# SCH_DC_Speed_controller_PWM_avarage_volt.net
KiCad netlist of a schematic drawn in EasyEDA
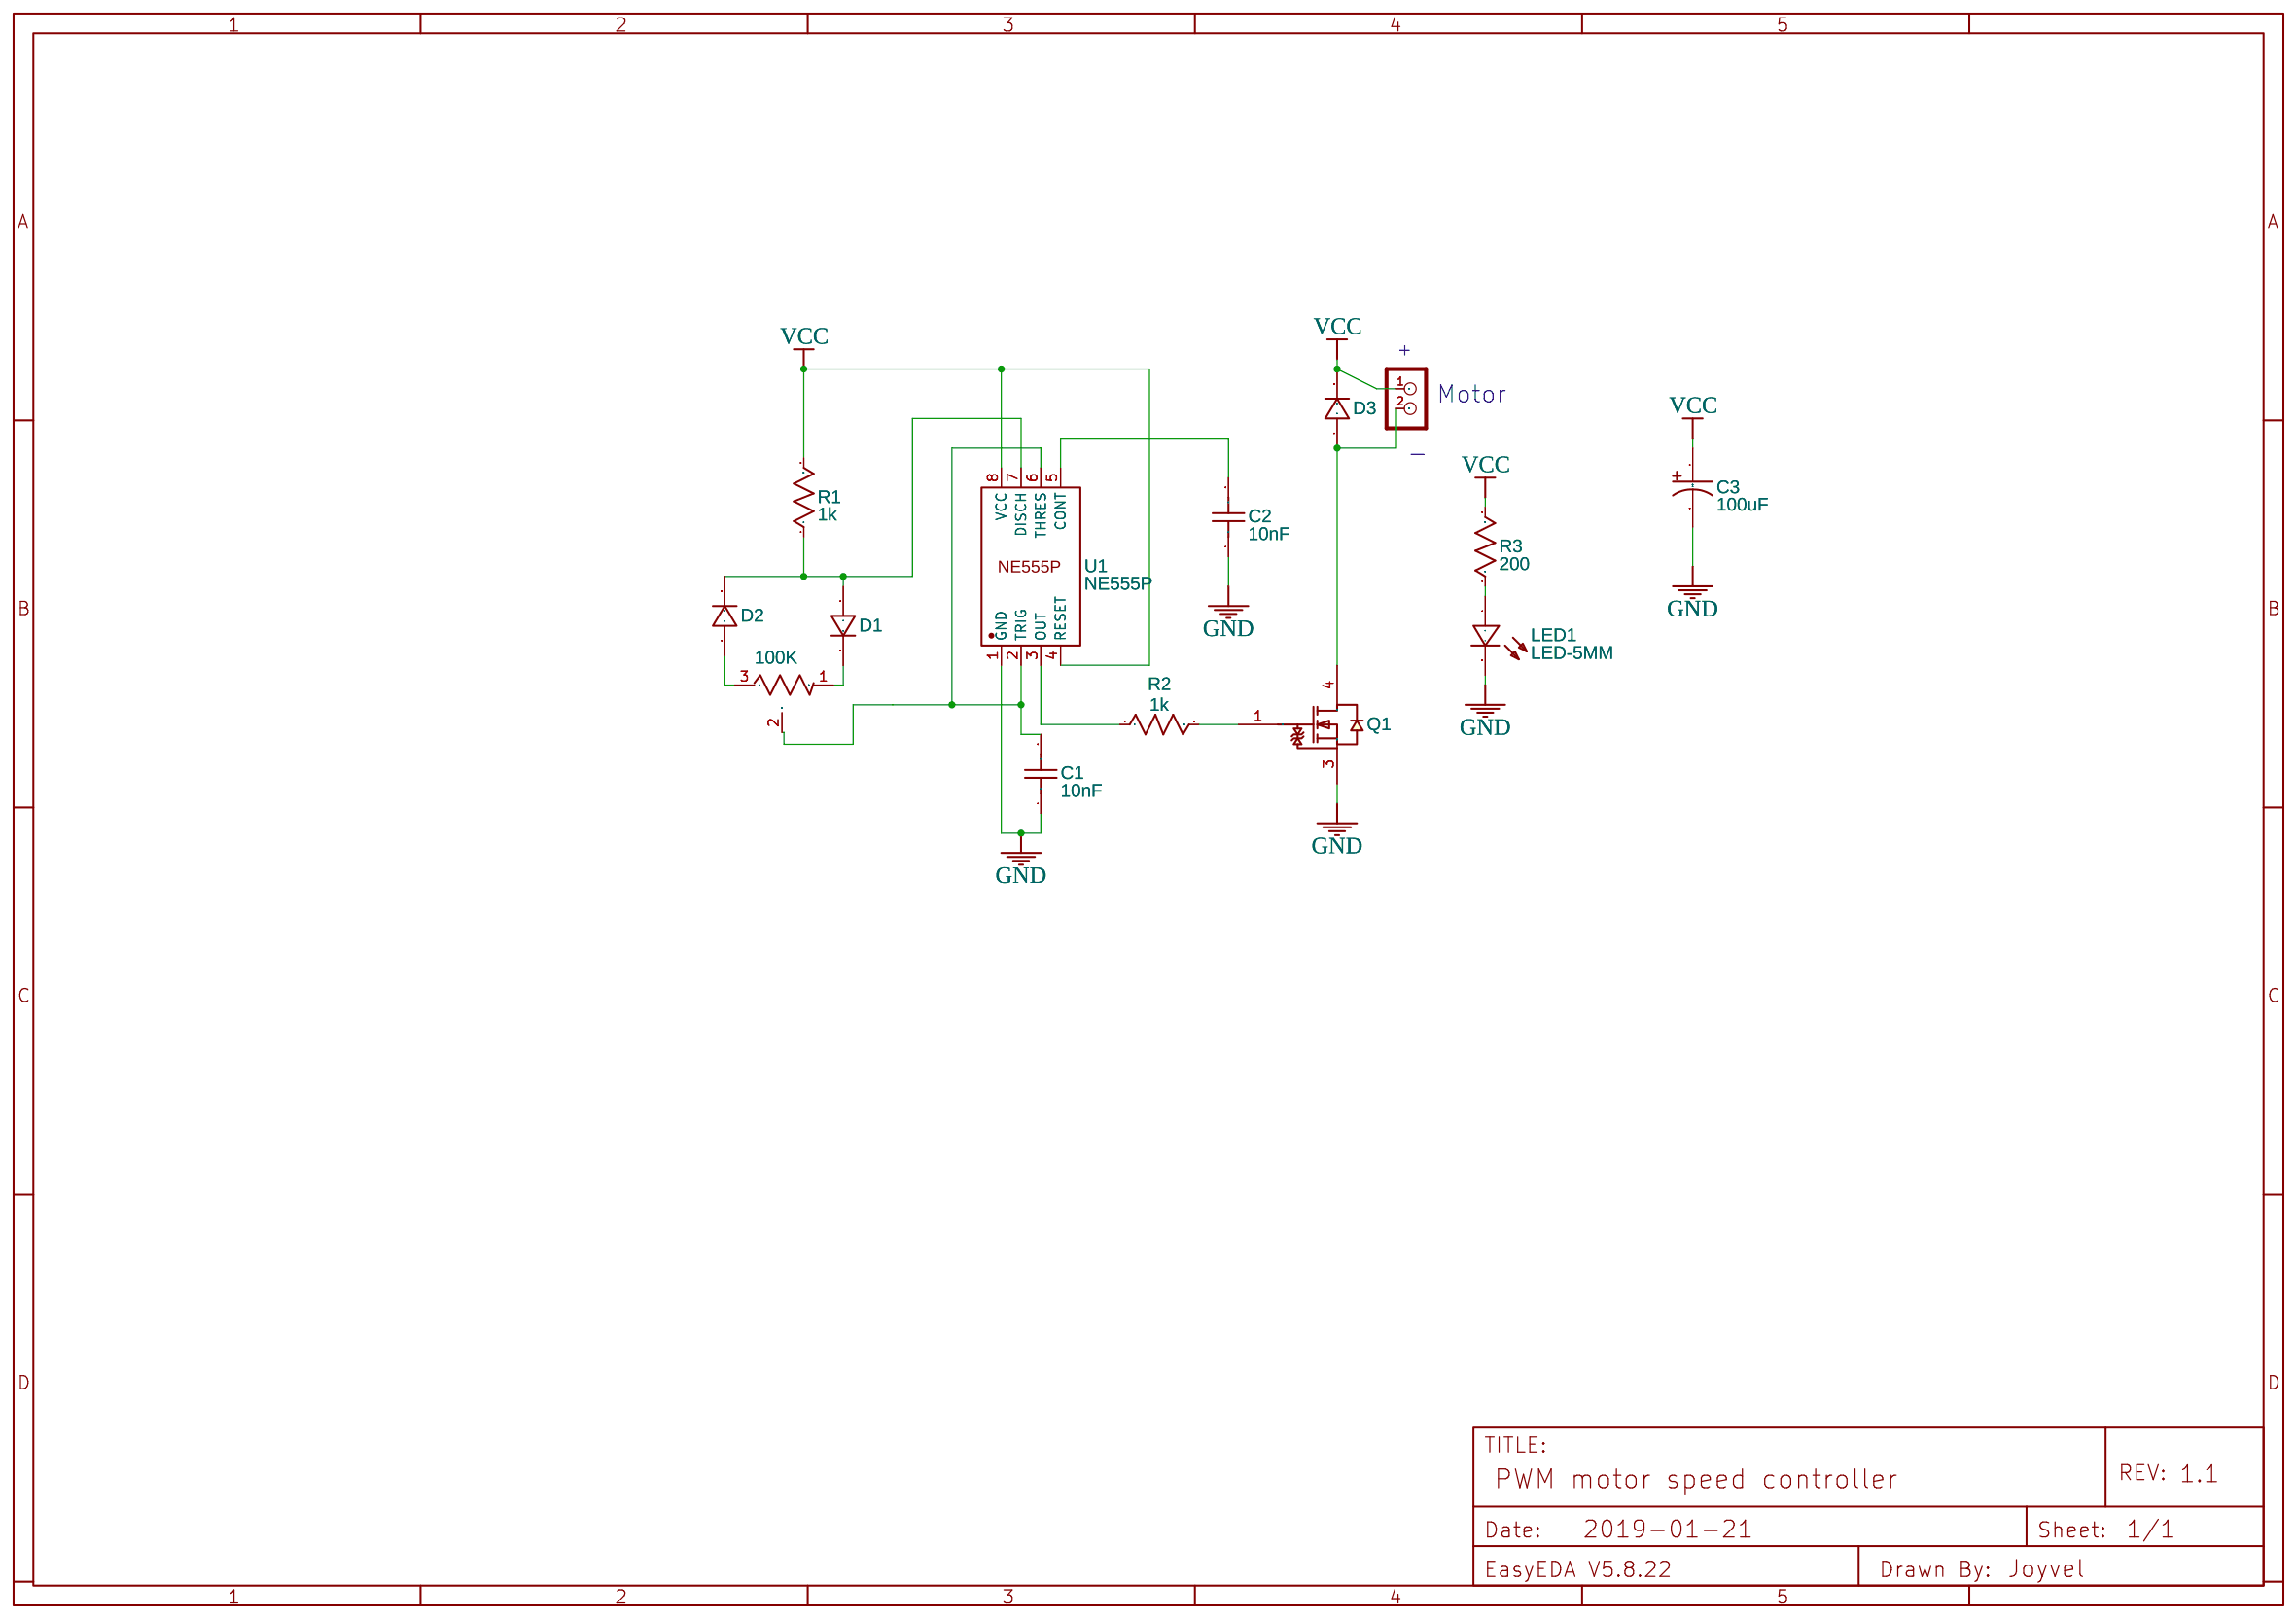
[diagram p0: schematic sheet]

(export (version "E")
  (design (tool "Eeschema 10.0.6"))
  (components
    (comp (ref "100K")
      (value "100K")
      (fields (field (name "Manufacturer Part") "?"))
      (libsource (lib "") (part "Unknown_405_340"))
    )
    (comp (ref "C1")
      (value "10nF")
      (fields (field (name "Manufacturer Part") "?"))
      (libsource (lib "") (part "Cap_RAD-0.1_US"))
    )
    (comp (ref "C2")
      (value "10nF")
      (fields (field (name "Manufacturer Part") "?"))
      (libsource (lib "") (part "Cap_RAD-0.1_US"))
    )
    (comp (ref "C3")
      (value "100uF")
      (fields (field (name "Manufacturer Part") "?"))
      (libsource (lib "") (part "Cap_Electrolytic(TH)_D3.0XF1.5_US"))
    )
    (comp (ref "D1")
      (value "1N4448")
      (fields (field (name "Manufacturer") "SEMTECH"))
      (libsource (lib "") (part "Unknown_420_310"))
    )
    (comp (ref "D2")
      (value "1N4448")
      (fields (field (name "Manufacturer") "SEMTECH"))
      (libsource (lib "") (part "Unknown_360_305"))
    )
    (comp (ref "D3")
      (value "0")
      (fields (field (name "Manufacturer Part") "1N4448") (field (name "Manufacturer") "SEMTECH"))
      (libsource (lib "") (part "Unknown_670_200"))
    )
    (comp (ref "J1")
      (value "CON_TERMINAL_BLOCK_02")
      (fields (field (name "Manufacturer Part") "?"))
      (libsource (lib "") (part "Unknown_705_195"))
    )
    (comp (ref "LED1")
      (value "LED-5MM")
      (fields (field (name "Manufacturer Part") "5AR2ST10") (field (name "Manufacturer") "EVERLIGHT"))
      (libsource (lib "") (part "Unknown_750_315"))
    )
    (comp (ref "Q1")
      (value "2SK4065-DL-1E")
      (fields (field (name "Manufacturer Part") "?"))
      (libsource (lib "") (part "Unknown_650_360"))
    )
    (comp (ref "R1")
      (value "1k")
      (fields (field (name "Manufacturer Part") "?"))
      (libsource (lib "") (part "Res_AXIAL-0.3(1/8W)_US"))
    )
    (comp (ref "R2")
      (value "1k")
      (fields (field (name "Manufacturer Part") "?"))
      (libsource (lib "") (part "Res_AXIAL-0.3(1/8W)_US_1"))
    )
    (comp (ref "R3")
      (value "200")
      (fields (field (name "Manufacturer Part") "?"))
      (libsource (lib "") (part "Res_AXIAL-0.3(1/8W)_US"))
    )
    (comp (ref "U1")
      (value "NE555P")
      (fields (field (name "Manufacturer") "TI"))
      (libsource (lib "") (part "Unknown_515_280"))
    )
  )
  (nets
    (net (code "1") (name "GND") (class "Default")
      (node (ref "C1") (pin "1") (pinfunction "1_1") (pintype "unspecified"))
      (node (ref "C2") (pin "1") (pinfunction "1_1") (pintype "unspecified"))
      (node (ref "C3") (pin "2") (pinfunction "2_2") (pintype "unspecified"))
      (node (ref "LED1") (pin "2") (pinfunction "-_2") (pintype "unspecified"))
      (node (ref "Q1") (pin "3") (pinfunction "S_3") (pintype "unspecified"))
      (node (ref "U1") (pin "1") (pinfunction "GND_1") (pintype "unspecified"))
    )
    (net (code "2") (name "Net-(D1-A)") (class "Default")
      (node (ref "D1") (pin "1") (pinfunction "A_1") (pintype "unspecified"))
      (node (ref "D2") (pin "2") (pinfunction "K_2") (pintype "unspecified"))
      (node (ref "R1") (pin "1") (pinfunction "1_1") (pintype "unspecified"))
      (node (ref "U1") (pin "7") (pinfunction "DISCH_7") (pintype "unspecified"))
    )
    (net (code "3") (name "Net-(D1-K)") (class "Default")
      (node (ref "100K") (pin "1") (pinfunction "1_1") (pintype "unspecified"))
      (node (ref "D1") (pin "2") (pinfunction "K_2") (pintype "unspecified"))
    )
    (net (code "4") (name "Net-(D2-A)") (class "Default")
      (node (ref "100K") (pin "3") (pinfunction "3_3") (pintype "unspecified"))
      (node (ref "D2") (pin "1") (pinfunction "A_1") (pintype "unspecified"))
    )
    (net (code "5") (name "Net-(D3-A)") (class "Default")
      (node (ref "D3") (pin "1") (pinfunction "A_1") (pintype "unspecified"))
      (node (ref "J1") (pin "2") (pinfunction "2_2") (pintype "unspecified"))
      (node (ref "Q1") (pin "4") (pinfunction "D_4") (pintype "unspecified"))
    )
    (net (code "6") (name "Net-(LED1-+)") (class "Default")
      (node (ref "LED1") (pin "1") (pinfunction "+_1") (pintype "unspecified"))
      (node (ref "R3") (pin "1") (pinfunction "1_1") (pintype "unspecified"))
    )
    (net (code "7") (name "Net-(Q1-G)") (class "Default")
      (node (ref "Q1") (pin "1") (pinfunction "G_1") (pintype "unspecified"))
      (node (ref "R2") (pin "2") (pinfunction "2_2") (pintype "unspecified"))
    )
    (net (code "8") (name "Net-(U1-CONT)") (class "Default")
      (node (ref "C2") (pin "2") (pinfunction "2_2") (pintype "unspecified"))
      (node (ref "U1") (pin "5") (pinfunction "CONT_5") (pintype "unspecified"))
    )
    (net (code "9") (name "Net-(U1-OUT)") (class "Default")
      (node (ref "R2") (pin "1") (pinfunction "1_1") (pintype "unspecified"))
      (node (ref "U1") (pin "3") (pinfunction "OUT_3") (pintype "unspecified"))
    )
    (net (code "10") (name "Net-(U1-THRES)") (class "Default")
      (node (ref "100K") (pin "2") (pinfunction "2_2") (pintype "unspecified"))
      (node (ref "C1") (pin "2") (pinfunction "2_2") (pintype "unspecified"))
      (node (ref "U1") (pin "2") (pinfunction "TRIG_2") (pintype "unspecified"))
      (node (ref "U1") (pin "6") (pinfunction "THRES_6") (pintype "unspecified"))
    )
    (net (code "11") (name "VCC") (class "Default")
      (node (ref "C3") (pin "1") (pinfunction "1_1") (pintype "unspecified"))
      (node (ref "D3") (pin "2") (pinfunction "K_2") (pintype "unspecified"))
      (node (ref "J1") (pin "1") (pinfunction "1_1") (pintype "unspecified"))
      (node (ref "R1") (pin "2") (pinfunction "2_2") (pintype "unspecified"))
      (node (ref "R3") (pin "2") (pinfunction "2_2") (pintype "unspecified"))
      (node (ref "U1") (pin "4") (pinfunction "RESET_4") (pintype "unspecified"))
      (node (ref "U1") (pin "8") (pinfunction "VCC_8") (pintype "unspecified"))
    )
  )
)
